# AdamCapteurs-1.net
KiCad netlist of a schematic drawn in Altium Designer
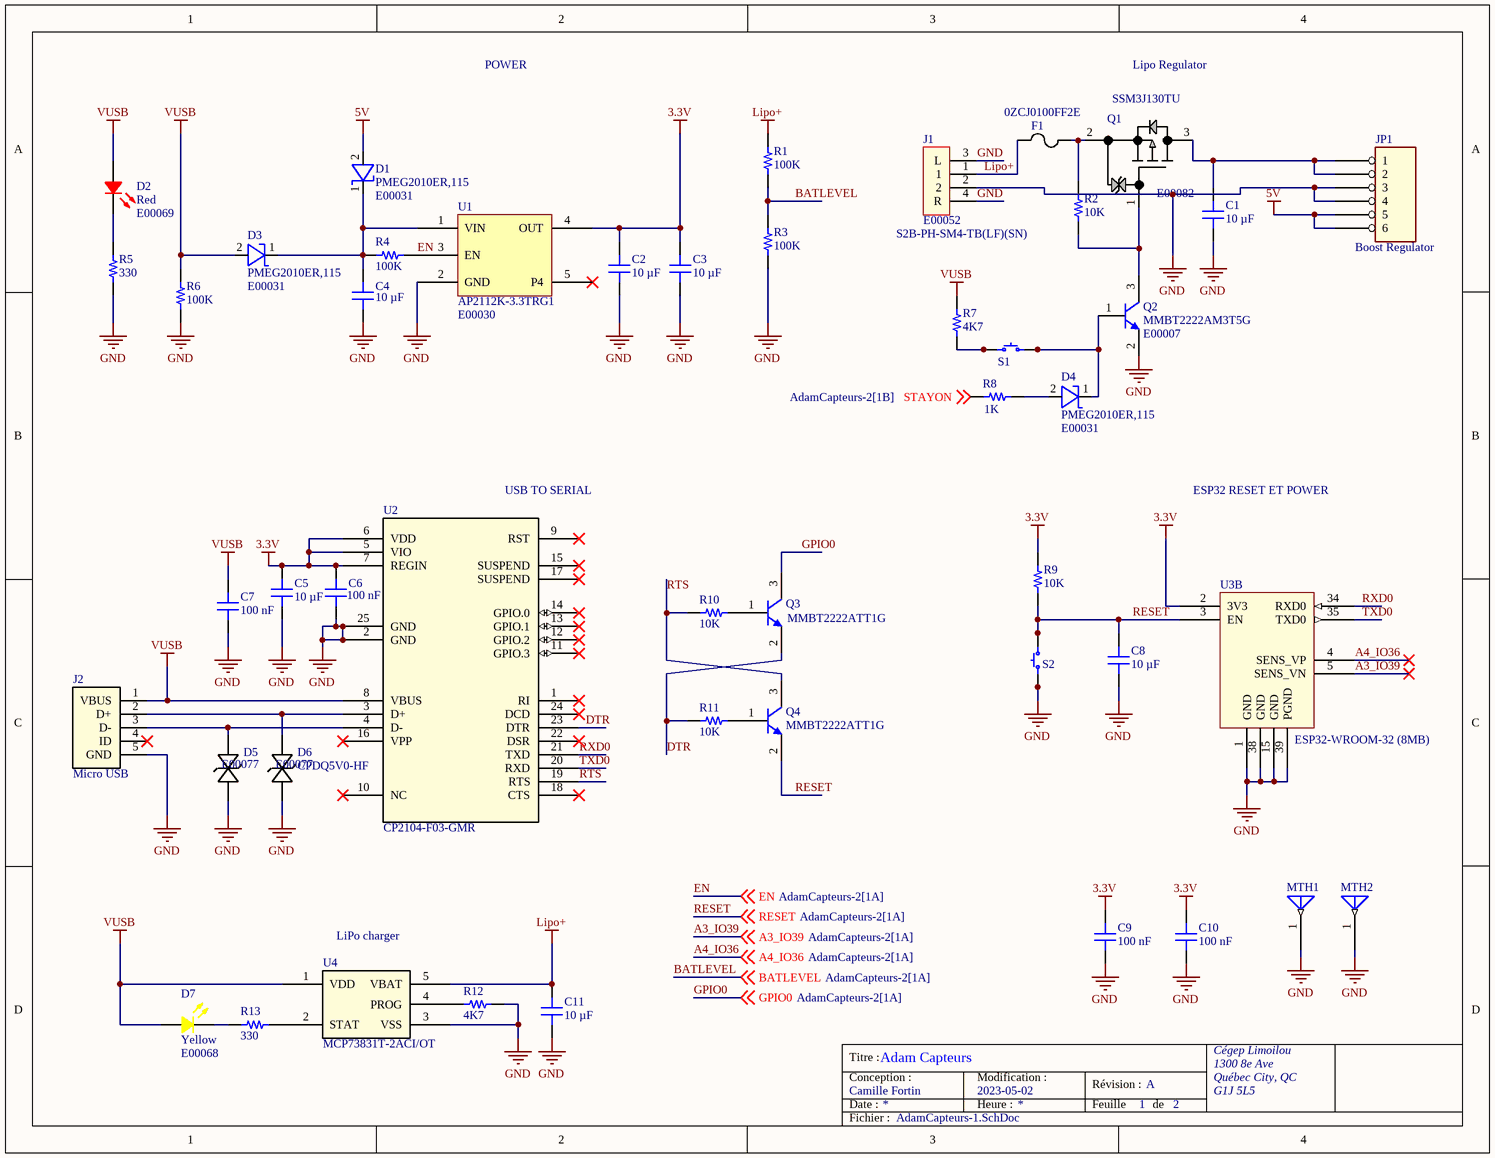
[diagram p0: AdamCapteurs-1.SchDoc]

(export (version "E")
  (design (tool "Eeschema 10.0.6"))
  (components
    (comp (ref "C1")
      (value "10 µF")
      (footprint "CAP 0603")
      (description "CAP CER 10UF 10V X6S 0603")
      (fields
        (field (name "PART NUMBER") "GRM188C81A106MA73D")
        (field (name "MANUFACTURER") "Murata Electronics")
      )
      (libsource (lib "ADAM LIBRARY") (part "Capacitor"))
    )
    (comp (ref "C2")
      (value "10 µF")
      (footprint "CAP 0603")
      (description "CAP CER 10UF 10V X6S 0603")
      (fields
        (field (name "PART NUMBER") "GRM188C81A106MA73D")
        (field (name "MANUFACTURER") "Murata Electronics")
      )
      (libsource (lib "ADAM LIBRARY") (part "Capacitor"))
    )
    (comp (ref "C3")
      (value "10 µF")
      (footprint "CAP 0603")
      (description "CAP CER 10UF 10V X6S 0603")
      (fields
        (field (name "PART NUMBER") "GRM188C81A106MA73D")
        (field (name "MANUFACTURER") "Murata Electronics")
      )
      (libsource (lib "ADAM LIBRARY") (part "Capacitor"))
    )
    (comp (ref "C4")
      (value "10 µF")
      (footprint "CAP 0603")
      (description "CAP CER 10UF 10V X6S 0603")
      (fields
        (field (name "PART NUMBER") "GRM188C81A106MA73D")
        (field (name "MANUFACTURER") "Murata Electronics")
      )
      (libsource (lib "ADAM LIBRARY") (part "Capacitor"))
    )
    (comp (ref "C5")
      (value "10 µF")
      (footprint "CAP 0603")
      (description "CAP CER 10UF 10V X6S 0603")
      (fields
        (field (name "PART NUMBER") "GRM188C81A106MA73D")
        (field (name "MANUFACTURER") "Murata Electronics")
      )
      (libsource (lib "ADAM LIBRARY") (part "Capacitor"))
    )
    (comp (ref "C6")
      (value "100 nF")
      (footprint "CAP 0603")
      (description "CAP CER 10UF 10V X6S 0603")
      (fields
        (field (name "PART NUMBER") "GRM188C81A106MA73D")
        (field (name "MANUFACTURER") "Murata Electronics")
      )
      (libsource (lib "ADAM LIBRARY") (part "Capacitor"))
    )
    (comp (ref "C7")
      (value "100 nF")
      (footprint "CAP 0603")
      (description "CAP CER 10UF 10V X6S 0603")
      (fields
        (field (name "PART NUMBER") "GRM188C81A106MA73D")
        (field (name "MANUFACTURER") "Murata Electronics")
      )
      (libsource (lib "ADAM LIBRARY") (part "Capacitor"))
    )
    (comp (ref "C8")
      (value "10 µF")
      (footprint "CAP 0603")
      (description "CAP CER 10UF 10V X6S 0603")
      (fields
        (field (name "PART NUMBER") "GRM188C81A106MA73D")
        (field (name "MANUFACTURER") "Murata Electronics")
      )
      (libsource (lib "ADAM LIBRARY") (part "Capacitor"))
    )
    (comp (ref "C9")
      (value "100 nF")
      (footprint "CAP 0603")
      (description "CAP CER 10UF 10V X6S 0603")
      (fields
        (field (name "PART NUMBER") "GRM188C81A106MA73D")
        (field (name "MANUFACTURER") "Murata Electronics")
      )
      (libsource (lib "ADAM LIBRARY") (part "Capacitor"))
    )
    (comp (ref "C10")
      (value "100 nF")
      (footprint "CAP 0603")
      (description "CAP CER 10UF 10V X6S 0603")
      (fields
        (field (name "PART NUMBER") "GRM188C81A106MA73D")
        (field (name "MANUFACTURER") "Murata Electronics")
      )
      (libsource (lib "ADAM LIBRARY") (part "Capacitor"))
    )
    (comp (ref "C11")
      (value "10 µF")
      (footprint "CAP 0603")
      (description "CAP CER 10UF 10V X6S 0603")
      (fields
        (field (name "PART NUMBER") "GRM188C81A106MA73D")
        (field (name "MANUFACTURER") "Murata Electronics")
      )
      (libsource (lib "ADAM LIBRARY") (part "Capacitor"))
    )
    (comp (ref "D1")
      (value "PMEG2010ER,115")
      (footprint "DIODE_PMEG2010ER,115_NEX")
      (description "Diode shotkey")
      (fields (field (name "ADAM INVENTORY NUMBER 1") "E00031"))
      (libsource (lib "ADAM LIBRARY") (part "PMEG2010ER,115"))
    )
    (comp (ref "D2")
      (value "Red")
      (footprint "Red Led 0603")
      (description "0603 RED LED")
      (fields
        (field (name "MANUFACTURER") "American Bright Optoelectronics Corporation")
        (field (name "ADAM INVENTORY NUMBER 1") "E00069")
      )
      (libsource (lib "ADAM LIBRARY") (part "0603 RED LED"))
    )
    (comp (ref "D3")
      (value "PMEG2010ER,115")
      (footprint "DIODE_PMEG2010ER,115_NEX")
      (description "Diode shotkey")
      (fields (field (name "ADAM INVENTORY NUMBER 1") "E00031"))
      (libsource (lib "ADAM LIBRARY") (part "PMEG2010ER,115"))
    )
    (comp (ref "D4")
      (value "PMEG2010ER,115")
      (footprint "DIODE_PMEG2010ER,115_NEX")
      (description "Diode shotkey")
      (fields (field (name "ADAM INVENTORY NUMBER 1") "E00031"))
      (libsource (lib "ADAM LIBRARY") (part "PMEG2010ER,115"))
    )
    (comp (ref "D5")
      (value "CPDQ5V0-HF")
      (footprint "CPDQ")
      (description "Diode TVS bidirectionnel")
      (fields (field (name "ADAM INVENTORY NUMBER 1") "E00077"))
      (libsource (lib "ADAM LIBRARY") (part "CPDQ5V0-HF"))
    )
    (comp (ref "D6")
      (value "CPDQ5V0-HF")
      (footprint "CPDQ")
      (description "Diode TVS bidirectionnel")
      (fields (field (name "ADAM INVENTORY NUMBER 1") "E00077"))
      (libsource (lib "ADAM LIBRARY") (part "CPDQ5V0-HF"))
    )
    (comp (ref "D7")
      (value "Yellow")
      (footprint "YELLOW LED 0603 - duplicate")
      (description "0603 YELLOW")
      (fields
        (field (name "MANUFACTURER") "American Bright Optoelectronics Corporation")
        (field (name "ADAM INVENTORY NUMBER 1") "E00068")
      )
      (libsource (lib "ADAM LIBRARY") (part "0603 YELLOW LED"))
    )
    (comp (ref "F1")
      (value "0ZCJ0100FF2E")
      (footprint "FUSE_NANOSMDCH030F/24-02_LTF")
      (description "Polyswitch 1A 5V")
      (fields (field (name "MANUFACTURER PART NUMBER 1") "0ZCJ0100FF2E"))
      (libsource (lib "ADAM LIBRARY") (part "0ZCJ0100FF2E"))
    )
    (comp (ref "J1")
      (value "CONN JST 2P SM 90DEG")
      (footprint "S2B-PH-SM4-TB_LF__SN")
      (description "CONN SM JST 2P")
      (fields
        (field (name "ADAM INVENTORY NUMBER 1") "E00052")
        (field (name "SUPPLIER PART NUMBER 1") "S2B-PH-SM4-TB(LF)(SN)")
        (field (name "COPYRIGHT") "Copyright (C) 2023 Ultra Librarian. All rights reserved.")
      )
      (libsource (lib "ADAM LIBRARY") (part "CONN JST 2P SM 90DEG"))
    )
    (comp (ref "J2")
      (value "Micro USB")
      (footprint "CONN_1050170001_MOL")
      (description "No Description Available")
      (fields (field (name "COPYRIGHT") "Copyright (C) 2023 Ultra Librarian. All rights reserved."))
      (libsource (lib "ADAM LIBRARY") (part "1050170001"))
    )
    (comp (ref "JP1")
      (value "Boost Regulator")
      (footprint "HDR1X6-Power")
      (libsource (lib "ADAM LIBRARY") (part "HEADER 6"))
    )
    (comp (ref "MTH1")
      (value "HOLE")
      (footprint "MNT_hole")
      (libsource (lib "ADAM LIBRARY") (part "ANTENNA"))
    )
    (comp (ref "MTH2")
      (value "HOLE")
      (footprint "MNT_hole")
      (libsource (lib "ADAM LIBRARY") (part "ANTENNA"))
    )
    (comp (ref "Q1")
      (value "SSM3J130TU")
      (footprint "UFM_TOS")
      (description "No Description Available")
      (fields (field (name "ADAM INVENTORY PART NUMBER") "E00082"))
      (libsource (lib "ADAM LIBRARY") (part "SSM3J130TU,LF"))
    )
    (comp (ref "Q2")
      (value "MMBT2222AM3T5G")
      (footprint "SOT-723")
      (description "TRANS NPN 40V 0.6A SOT-723")
      (fields
        (field (name "MANUFACTURER") "ON Semiconductor")
        (field (name "ADAM INVENTORY NUMBER 1") "E00007")
      )
      (libsource (lib "ADAM LIBRARY") (part "TRANS NPN 40V"))
    )
    (comp (ref "Q3")
      (value "MMBT2222ATT1G")
      (footprint "SOT-416_1P65X0P9_ONS-M")
      (description "TRANS NPN 40V 0.6A SC75-3")
      (fields (field (name "MANUFACTURER") "ON Semiconductor"))
      (libsource (lib "ADAM LIBRARY") (part "ON SEMI NPN SC-75"))
    )
    (comp (ref "Q4")
      (value "MMBT2222ATT1G")
      (footprint "SOT-416_1P65X0P9_ONS-M")
      (description "TRANS NPN 40V 0.6A SC75-3")
      (fields (field (name "MANUFACTURER") "ON Semiconductor"))
      (libsource (lib "ADAM LIBRARY") (part "ON SEMI NPN SC-75"))
    )
    (comp (ref "R1")
      (value "100K")
      (footprint "RES 0603")
      (description "RES SMD 100K OHM 0.1% 1/16W 0603")
      (fields
        (field (name "PART NUMBER") "CPF0603B100KE")
        (field (name "MANUFACTURER") "TE Connectivity Passive Product")
      )
      (libsource (lib "ADAM LIBRARY") (part "Resistor"))
    )
    (comp (ref "R2")
      (value "10K")
      (footprint "RES 0603")
      (description "RES SMD 100K OHM 0.1% 1/16W 0603")
      (fields
        (field (name "PART NUMBER") "CPF0603B100KE")
        (field (name "MANUFACTURER") "TE Connectivity Passive Product")
      )
      (libsource (lib "ADAM LIBRARY") (part "Resistor"))
    )
    (comp (ref "R3")
      (value "100K")
      (footprint "RES 0603")
      (description "RES SMD 100K OHM 0.1% 1/16W 0603")
      (fields
        (field (name "PART NUMBER") "CPF0603B100KE")
        (field (name "MANUFACTURER") "TE Connectivity Passive Product")
      )
      (libsource (lib "ADAM LIBRARY") (part "Resistor"))
    )
    (comp (ref "R4")
      (value "100K")
      (footprint "RES 0603")
      (description "RES SMD 100K OHM 0.1% 1/16W 0603")
      (fields
        (field (name "PART NUMBER") "CPF0603B100KE")
        (field (name "MANUFACTURER") "TE Connectivity Passive Product")
      )
      (libsource (lib "ADAM LIBRARY") (part "Resistor"))
    )
    (comp (ref "R5")
      (value "330")
      (footprint "RES 0603")
      (description "RES SMD 1K OHM 0.1% 1/16W 0603")
      (fields
        (field (name "PART NUMBER") "CPF0603B1K0E")
        (field (name "MANUFACTURER") "TE Connectivity Passive Product")
      )
      (libsource (lib "ADAM LIBRARY") (part "Resistor"))
    )
    (comp (ref "R6")
      (value "100K")
      (footprint "RES 0603")
      (description "RES SMD 100K OHM 0.1% 1/16W 0603")
      (fields
        (field (name "PART NUMBER") "CPF0603B100KE")
        (field (name "MANUFACTURER") "TE Connectivity Passive Product")
      )
      (libsource (lib "ADAM LIBRARY") (part "Resistor"))
    )
    (comp (ref "R7")
      (value "4K7")
      (footprint "RES 0603")
      (description "RES SMD 100K OHM 0.1% 1/16W 0603")
      (fields
        (field (name "PART NUMBER") "CPF0603B100KE")
        (field (name "MANUFACTURER") "TE Connectivity Passive Product")
      )
      (libsource (lib "ADAM LIBRARY") (part "Resistor"))
    )
    (comp (ref "R8")
      (value "1K")
      (footprint "RES 0603")
      (description "RES SMD 100K OHM 0.1% 1/16W 0603")
      (fields
        (field (name "PART NUMBER") "CPF0603B100KE")
        (field (name "MANUFACTURER") "TE Connectivity Passive Product")
      )
      (libsource (lib "ADAM LIBRARY") (part "Resistor"))
    )
    (comp (ref "R9")
      (value "10K")
      (footprint "RES 0603")
      (description "RES 10K OHM 0.1% 1/16W 0603")
      (fields
        (field (name "PART NUMBER") "RNCS0603BKE10K0")
        (field (name "MANUFACTURER") "Stackpole Electronics Inc")
      )
      (libsource (lib "ADAM LIBRARY") (part "Resistor"))
    )
    (comp (ref "R10")
      (value "10K")
      (footprint "RES 0603")
      (description "RES 10K OHM 0.1% 1/16W 0603")
      (fields
        (field (name "PART NUMBER") "RNCS0603BKE10K0")
        (field (name "MANUFACTURER") "Stackpole Electronics Inc")
      )
      (libsource (lib "ADAM LIBRARY") (part "Resistor"))
    )
    (comp (ref "R11")
      (value "10K")
      (footprint "RES 0603")
      (description "RES 10K OHM 0.1% 1/16W 0603")
      (fields
        (field (name "PART NUMBER") "RNCS0603BKE10K0")
        (field (name "MANUFACTURER") "Stackpole Electronics Inc")
      )
      (libsource (lib "ADAM LIBRARY") (part "Resistor"))
    )
    (comp (ref "R12")
      (value "4K7")
      (footprint "RES 0603")
      (description "RES SMD 4.7K OHM 1% 1/10W 0603")
      (fields (field (name "PART NUMBER") "RT0603FRE074K7L") (field (name "MANUFACTURER") "Yageo"))
      (libsource (lib "ADAM LIBRARY") (part "Resistor"))
    )
    (comp (ref "R13")
      (value "330")
      (footprint "RES 0603")
      (description "RES SMD 1K OHM 0.1% 1/16W 0603")
      (fields
        (field (name "PART NUMBER") "CPF0603B1K0E")
        (field (name "MANUFACTURER") "TE Connectivity Passive Product")
      )
      (libsource (lib "ADAM LIBRARY") (part "Resistor"))
    )
    (comp (ref "S1")
      (value "KMR741NG ULC LFS")
      (footprint "Switch Lin SMD")
      (description "SWITCH TACTILE SPST-NO 50MA 32V")
      (fields (field (name "MANUFACTURER") "C&K"))
      (libsource (lib "ADAM LIBRARY") (part "SPST-NO 4 PIN"))
    )
    (comp (ref "S2")
      (value "KMR741NG ULC LFS")
      (footprint "Switch Lin SMD")
      (description "SWITCH TACTILE SPST-NO 50MA 32V")
      (fields (field (name "MANUFACTURER") "C&K"))
      (libsource (lib "ADAM LIBRARY") (part "SPST-NO 4 PIN"))
    )
    (comp (ref "U1")
      (value "AP2112K-3.3TRG1")
      (description "REG LINEAIRE 3.3V")
      (fields (field (name "ADAM INVENTORY NUMBER 1") "E00030"))
      (libsource (lib "ADAM LIBRARY") (part "REG LIN 3.3V"))
    )
    (comp (ref "U2")
      (value "CP2104-F03-GMR")
      (footprint "QFN_F03-GMR_SIL-M")
      (description "No Description Available")
      (fields (field (name "COPYRIGHT") "Copyright (C) 2023 Ultra Librarian. All rights reserved."))
      (libsource (lib "ADAM LIBRARY") (part "CP2104-F03-GMR"))
    )
    (comp (ref "U3")
      (value "ESP32-WROOM-32 (8MB)")
      (footprint "ESP32-WROOM-32D")
      (description "No Description Available")
      (fields (field (name "COPYRIGHT") "Copyright (C) 2023 Ultra Librarian. All rights reserved."))
      (libsource (lib "ADAM LIBRARY") (part "ESP32-WROOM-32 (8MB)"))
    )
    (comp (ref "U4")
      (value "MCP73831T-2ACI/OT")
      (footprint "SOT23_MCP73831T-2ACI/OT_HNW")
      (description "No Description Available")
      (fields (field (name "COPYRIGHT") "Copyright (C) 2023 Ultra Librarian. All rights reserved."))
      (libsource (lib "ADAM LIBRARY") (part "MCP73831T-2ACI/OT"))
    )
  )
  (nets
    (net (code "1") (name "/DTR") (class "Default")
      (node (ref "Q3") (pin "2") (pinfunction "E_2") (pintype "passive"))
      (node (ref "R11") (pin "2") (pinfunction "2_2") (pintype "passive"))
      (node (ref "U2") (pin "23") (pinfunction "DTR_23") (pintype "passive"))
    )
    (net (code "2") (name "/RTS") (class "Default")
      (node (ref "Q4") (pin "3") (pinfunction "C_3") (pintype "passive"))
      (node (ref "R10") (pin "2") (pinfunction "2_2") (pintype "passive"))
      (node (ref "U2") (pin "19") (pinfunction "RTS_19") (pintype "passive"))
    )
    (net (code "3") (name "/RXD0") (class "Default")
      (node (ref "U2") (pin "21") (pinfunction "TXD_21") (pintype "passive"))
      (node (ref "U3") (pin "34") (pinfunction "RXD0_34") (pintype "input"))
    )
    (net (code "4") (name "/TXD0") (class "Default")
      (node (ref "U2") (pin "20") (pinfunction "RXD_20") (pintype "passive"))
      (node (ref "U3") (pin "35") (pinfunction "TXD0_35") (pintype "output"))
    )
    (net (code "5") (name "3.3V") (class "Default")
      (node (ref "C10") (pin "2") (pinfunction "2_2") (pintype "passive"))
      (node (ref "C2") (pin "2") (pinfunction "2_2") (pintype "passive"))
      (node (ref "C3") (pin "2") (pinfunction "2_2") (pintype "passive"))
      (node (ref "C5") (pin "2") (pinfunction "2_2") (pintype "passive"))
      (node (ref "C6") (pin "2") (pinfunction "2_2") (pintype "passive"))
      (node (ref "C9") (pin "2") (pinfunction "2_2") (pintype "passive"))
      (node (ref "R9") (pin "2") (pinfunction "2_2") (pintype "passive"))
      (node (ref "U1") (pin "4") (pinfunction "OUT_4") (pintype "passive"))
      (node (ref "U2") (pin "5") (pinfunction "VIO_5") (pintype "passive"))
      (node (ref "U2") (pin "6") (pinfunction "VDD_6") (pintype "power_in"))
      (node (ref "U2") (pin "7") (pinfunction "REGIN_7") (pintype "passive"))
      (node (ref "U3") (pin "2") (pinfunction "3V3_2") (pintype "power_in"))
    )
    (net (code "6") (name "5V") (class "Default")
      (node (ref "D1") (pin "2") (pinfunction "A_2") (pintype "passive"))
      (node (ref "JP1") (pin "5") (pinfunction "5_5") (pintype "passive"))
      (node (ref "JP1") (pin "6") (pinfunction "6_6") (pintype "passive"))
    )
    (net (code "7") (name "A3_IO39") (class "Default")
      (node (ref "U3") (pin "5") (pinfunction "SENS_VN_5") (pintype "passive"))
    )
    (net (code "8") (name "A4_IO36") (class "Default")
      (node (ref "U3") (pin "4") (pinfunction "SENS_VP_4") (pintype "passive"))
    )
    (net (code "9") (name "BATLEVEL") (class "Default")
      (node (ref "R1") (pin "1") (pinfunction "1_1") (pintype "passive"))
      (node (ref "R3") (pin "2") (pinfunction "2_2") (pintype "passive"))
    )
    (net (code "10") (name "EN") (class "Default")
      (node (ref "R4") (pin "1") (pinfunction "1_1") (pintype "passive"))
      (node (ref "U1") (pin "3") (pinfunction "EN_3") (pintype "passive"))
    )
    (net (code "11") (name "GND") (class "Default")
      (node (ref "C1") (pin "1") (pinfunction "1_1") (pintype "passive"))
      (node (ref "C10") (pin "1") (pinfunction "1_1") (pintype "passive"))
      (node (ref "C11") (pin "1") (pinfunction "1_1") (pintype "passive"))
      (node (ref "C2") (pin "1") (pinfunction "1_1") (pintype "passive"))
      (node (ref "C3") (pin "1") (pinfunction "1_1") (pintype "passive"))
      (node (ref "C4") (pin "1") (pinfunction "1_1") (pintype "passive"))
      (node (ref "C5") (pin "1") (pinfunction "1_1") (pintype "passive"))
      (node (ref "C6") (pin "1") (pinfunction "1_1") (pintype "passive"))
      (node (ref "C7") (pin "1") (pinfunction "1_1") (pintype "passive"))
      (node (ref "C8") (pin "1") (pinfunction "1_1") (pintype "passive"))
      (node (ref "C9") (pin "1") (pinfunction "1_1") (pintype "passive"))
      (node (ref "D5") (pin "1") (pinfunction "1_1") (pintype "passive"))
      (node (ref "D6") (pin "1") (pinfunction "1_1") (pintype "passive"))
      (node (ref "J1") (pin "2") (pinfunction "2_2") (pintype "passive"))
      (node (ref "J1") (pin "3") (pinfunction "L_3") (pintype "passive"))
      (node (ref "J1") (pin "4") (pinfunction "R_4") (pintype "passive"))
      (node (ref "J2") (pin "5") (pinfunction "GND_5") (pintype "passive"))
      (node (ref "JP1") (pin "3") (pinfunction "3_3") (pintype "passive"))
      (node (ref "JP1") (pin "4") (pinfunction "4_4") (pintype "passive"))
      (node (ref "MTH1") (pin "1") (pinfunction "1_1") (pintype "output"))
      (node (ref "MTH2") (pin "1") (pinfunction "1_1") (pintype "output"))
      (node (ref "Q2") (pin "2") (pinfunction "E_2") (pintype "passive"))
      (node (ref "R12") (pin "2") (pinfunction "2_2") (pintype "passive"))
      (node (ref "R3") (pin "1") (pinfunction "1_1") (pintype "passive"))
      (node (ref "R5") (pin "2") (pinfunction "2_2") (pintype "passive"))
      (node (ref "R6") (pin "1") (pinfunction "1_1") (pintype "passive"))
      (node (ref "S2") (pin "1") (pinfunction "1_1") (pintype "passive"))
      (node (ref "S2") (pin "2") (pinfunction "2_2") (pintype "passive"))
      (node (ref "U1") (pin "2") (pinfunction "GND_2") (pintype "passive"))
      (node (ref "U2") (pin "2") (pinfunction "GND_2") (pintype "passive"))
      (node (ref "U2") (pin "25") (pinfunction "GND_25") (pintype "passive"))
      (node (ref "U3") (pin "1") (pinfunction "GND_1") (pintype "power_in"))
      (node (ref "U3") (pin "15") (pinfunction "GND_15") (pintype "power_in"))
      (node (ref "U3") (pin "38") (pinfunction "GND_38") (pintype "power_in"))
      (node (ref "U3") (pin "39") (pinfunction "PGND_39") (pintype "power_in"))
      (node (ref "U4") (pin "3") (pinfunction "VSS_3") (pintype "passive"))
    )
    (net (code "12") (name "GPIO0") (class "Default")
      (node (ref "Q3") (pin "3") (pinfunction "C_3") (pintype "passive"))
    )
    (net (code "13") (name "Lipo+") (class "Default")
      (node (ref "C11") (pin "2") (pinfunction "2_2") (pintype "passive"))
      (node (ref "F1") (pin "1") (pinfunction "1_1") (pintype "passive"))
      (node (ref "J1") (pin "1") (pinfunction "1_1") (pintype "passive"))
      (node (ref "R1") (pin "2") (pinfunction "2_2") (pintype "passive"))
      (node (ref "U4") (pin "5") (pinfunction "VBAT_5") (pintype "passive"))
    )
    (net (code "14") (name "Net-(C1-Pad2)") (class "Default")
      (node (ref "C1") (pin "2") (pinfunction "2_2") (pintype "passive"))
      (node (ref "JP1") (pin "1") (pinfunction "1_1") (pintype "passive"))
      (node (ref "JP1") (pin "2") (pinfunction "2_2") (pintype "passive"))
      (node (ref "Q1") (pin "3") (pinfunction "3_3") (pintype "passive"))
    )
    (net (code "15") (name "Net-(D1-K)") (class "Default")
      (node (ref "C4") (pin "2") (pinfunction "2_2") (pintype "passive"))
      (node (ref "D1") (pin "1") (pinfunction "K_1") (pintype "passive"))
      (node (ref "D3") (pin "1") (pinfunction "K_1") (pintype "passive"))
      (node (ref "R4") (pin "2") (pinfunction "2_2") (pintype "passive"))
      (node (ref "U1") (pin "1") (pinfunction "VIN_1") (pintype "passive"))
    )
    (net (code "16") (name "Net-(D2-Pad2)") (class "Default")
      (node (ref "D2") (pin "2") (pinfunction "2_2") (pintype "passive"))
      (node (ref "R5") (pin "1") (pinfunction "1_1") (pintype "passive"))
    )
    (net (code "17") (name "Net-(D4-A)") (class "Default")
      (node (ref "D4") (pin "2") (pinfunction "A_2") (pintype "passive"))
      (node (ref "R8") (pin "1") (pinfunction "1_1") (pintype "passive"))
    )
    (net (code "18") (name "Net-(D4-K)") (class "Default")
      (node (ref "D4") (pin "1") (pinfunction "K_1") (pintype "passive"))
      (node (ref "Q2") (pin "1") (pinfunction "B_1") (pintype "passive"))
      (node (ref "S1") (pin "3") (pinfunction "3_3") (pintype "passive"))
      (node (ref "S1") (pin "4") (pinfunction "4_4") (pintype "passive"))
    )
    (net (code "19") (name "Net-(D7-Pad2)") (class "Default")
      (node (ref "D7") (pin "2") (pinfunction "2_2") (pintype "passive"))
      (node (ref "R13") (pin "1") (pinfunction "1_1") (pintype "passive"))
    )
    (net (code "20") (name "Net-(F1-Pad2)") (class "Default")
      (node (ref "F1") (pin "2") (pinfunction "2_2") (pintype "passive"))
      (node (ref "Q1") (pin "2") (pinfunction "2_2") (pintype "passive"))
      (node (ref "R2") (pin "2") (pinfunction "2_2") (pintype "passive"))
    )
    (net (code "21") (name "Net-(J2-D+)") (class "Default")
      (node (ref "D6") (pin "2") (pinfunction "2_2") (pintype "passive"))
      (node (ref "J2") (pin "2") (pinfunction "D+_2") (pintype "passive"))
      (node (ref "U2") (pin "3") (pinfunction "D+_3") (pintype "passive"))
    )
    (net (code "22") (name "Net-(J2-D-)") (class "Default")
      (node (ref "D5") (pin "2") (pinfunction "2_2") (pintype "passive"))
      (node (ref "J2") (pin "3") (pinfunction "D-_3") (pintype "passive"))
      (node (ref "U2") (pin "4") (pinfunction "D-_4") (pintype "passive"))
    )
    (net (code "23") (name "Net-(Q2-C)") (class "Default")
      (node (ref "Q1") (pin "1") (pinfunction "1_1") (pintype "passive"))
      (node (ref "Q2") (pin "3") (pinfunction "C_3") (pintype "passive"))
      (node (ref "R2") (pin "1") (pinfunction "1_1") (pintype "passive"))
    )
    (net (code "24") (name "Net-(Q3-B)") (class "Default")
      (node (ref "Q3") (pin "1") (pinfunction "B_1") (pintype "passive"))
      (node (ref "R10") (pin "1") (pinfunction "1_1") (pintype "passive"))
    )
    (net (code "25") (name "Net-(Q4-B)") (class "Default")
      (node (ref "Q4") (pin "1") (pinfunction "B_1") (pintype "passive"))
      (node (ref "R11") (pin "1") (pinfunction "1_1") (pintype "passive"))
    )
    (net (code "26") (name "Net-(R7-Pad1)") (class "Default")
      (node (ref "R7") (pin "1") (pinfunction "1_1") (pintype "passive"))
      (node (ref "S1") (pin "1") (pinfunction "1_1") (pintype "passive"))
      (node (ref "S1") (pin "2") (pinfunction "2_2") (pintype "passive"))
    )
    (net (code "27") (name "Net-(U4-PROG)") (class "Default")
      (node (ref "R12") (pin "1") (pinfunction "1_1") (pintype "passive"))
      (node (ref "U4") (pin "4") (pinfunction "PROG_4") (pintype "passive"))
    )
    (net (code "28") (name "Net-(U4-STAT)") (class "Default")
      (node (ref "R13") (pin "2") (pinfunction "2_2") (pintype "passive"))
      (node (ref "U4") (pin "2") (pinfunction "STAT_2") (pintype "passive"))
    )
    (net (code "29") (name "RESET") (class "Default")
      (node (ref "C8") (pin "2") (pinfunction "2_2") (pintype "passive"))
      (node (ref "Q4") (pin "2") (pinfunction "E_2") (pintype "passive"))
      (node (ref "R9") (pin "1") (pinfunction "1_1") (pintype "passive"))
      (node (ref "S2") (pin "3") (pinfunction "3_3") (pintype "passive"))
      (node (ref "S2") (pin "4") (pinfunction "4_4") (pintype "passive"))
      (node (ref "U3") (pin "3") (pinfunction "EN_3") (pintype "passive"))
    )
    (net (code "30") (name "STAYON") (class "Default")
      (node (ref "R8") (pin "2") (pinfunction "2_2") (pintype "passive"))
    )
    (net (code "31") (name "VUSB") (class "Default")
      (node (ref "C7") (pin "2") (pinfunction "2_2") (pintype "passive"))
      (node (ref "D2") (pin "1") (pinfunction "1_1") (pintype "passive"))
      (node (ref "D3") (pin "2") (pinfunction "A_2") (pintype "passive"))
      (node (ref "D7") (pin "1") (pinfunction "1_1") (pintype "passive"))
      (node (ref "J2") (pin "1") (pinfunction "VBUS_1") (pintype "passive"))
      (node (ref "R6") (pin "2") (pinfunction "2_2") (pintype "passive"))
      (node (ref "R7") (pin "2") (pinfunction "2_2") (pintype "passive"))
      (node (ref "U2") (pin "8") (pinfunction "VBUS_8") (pintype "passive"))
      (node (ref "U4") (pin "1") (pinfunction "VDD_1") (pintype "passive"))
    )
    (net (code "32") (name "unconnected-(J2-ID-Pad4)") (class "Default")
      (node (ref "J2") (pin "4") (pinfunction "ID_4") (pintype "passive+no_connect"))
    )
    (net (code "33") (name "unconnected-(U1-P4-Pad5)") (class "Default")
      (node (ref "U1") (pin "5") (pinfunction "P4_5") (pintype "passive+no_connect"))
    )
    (net (code "34") (name "unconnected-(U2-CTS-Pad18)") (class "Default")
      (node (ref "U2") (pin "18") (pinfunction "CTS_18") (pintype "passive+no_connect"))
    )
    (net (code "35") (name "unconnected-(U2-DCD-Pad24)") (class "Default")
      (node (ref "U2") (pin "24") (pinfunction "DCD_24") (pintype "passive+no_connect"))
    )
    (net (code "36") (name "unconnected-(U2-DSR-Pad22)") (class "Default")
      (node (ref "U2") (pin "22") (pinfunction "DSR_22") (pintype "passive+no_connect"))
    )
    (net (code "37") (name "unconnected-(U2-GPIO.0-Pad14)") (class "Default")
      (node (ref "U2") (pin "14") (pinfunction "GPIO.0_14") (pintype "bidirectional+no_connect"))
    )
    (net (code "38") (name "unconnected-(U2-GPIO.1-Pad13)") (class "Default")
      (node (ref "U2") (pin "13") (pinfunction "GPIO.1_13") (pintype "bidirectional+no_connect"))
    )
    (net (code "39") (name "unconnected-(U2-GPIO.2-Pad12)") (class "Default")
      (node (ref "U2") (pin "12") (pinfunction "GPIO.2_12") (pintype "bidirectional+no_connect"))
    )
    (net (code "40") (name "unconnected-(U2-GPIO.3-Pad11)") (class "Default")
      (node (ref "U2") (pin "11") (pinfunction "GPIO.3_11") (pintype "bidirectional+no_connect"))
    )
    (net (code "41") (name "unconnected-(U2-NC-Pad10)") (class "Default")
      (node (ref "U2") (pin "10") (pinfunction "NC_10") (pintype "passive+no_connect"))
    )
    (net (code "42") (name "unconnected-(U2-RI-Pad1)") (class "Default")
      (node (ref "U2") (pin "1") (pinfunction "RI_1") (pintype "passive+no_connect"))
    )
    (net (code "43") (name "unconnected-(U2-RST-Pad9)") (class "Default")
      (node (ref "U2") (pin "9") (pinfunction "RST_9") (pintype "passive+no_connect"))
    )
    (net (code "44") (name "unconnected-(U2-SUSPEND-Pad15)") (class "Default")
      (node (ref "U2") (pin "15") (pinfunction "SUSPEND_15") (pintype "passive+no_connect"))
    )
    (net (code "45") (name "unconnected-(U2-SUSPEND-Pad17)") (class "Default")
      (node (ref "U2") (pin "17") (pinfunction "SUSPEND_17") (pintype "passive+no_connect"))
    )
    (net (code "46") (name "unconnected-(U2-VPP-Pad16)") (class "Default")
      (node (ref "U2") (pin "16") (pinfunction "VPP_16") (pintype "power_in+no_connect"))
    )
  )
)
